# Pulse_Oximeter.net
KiCad netlist of a schematic drawn in EAGLE
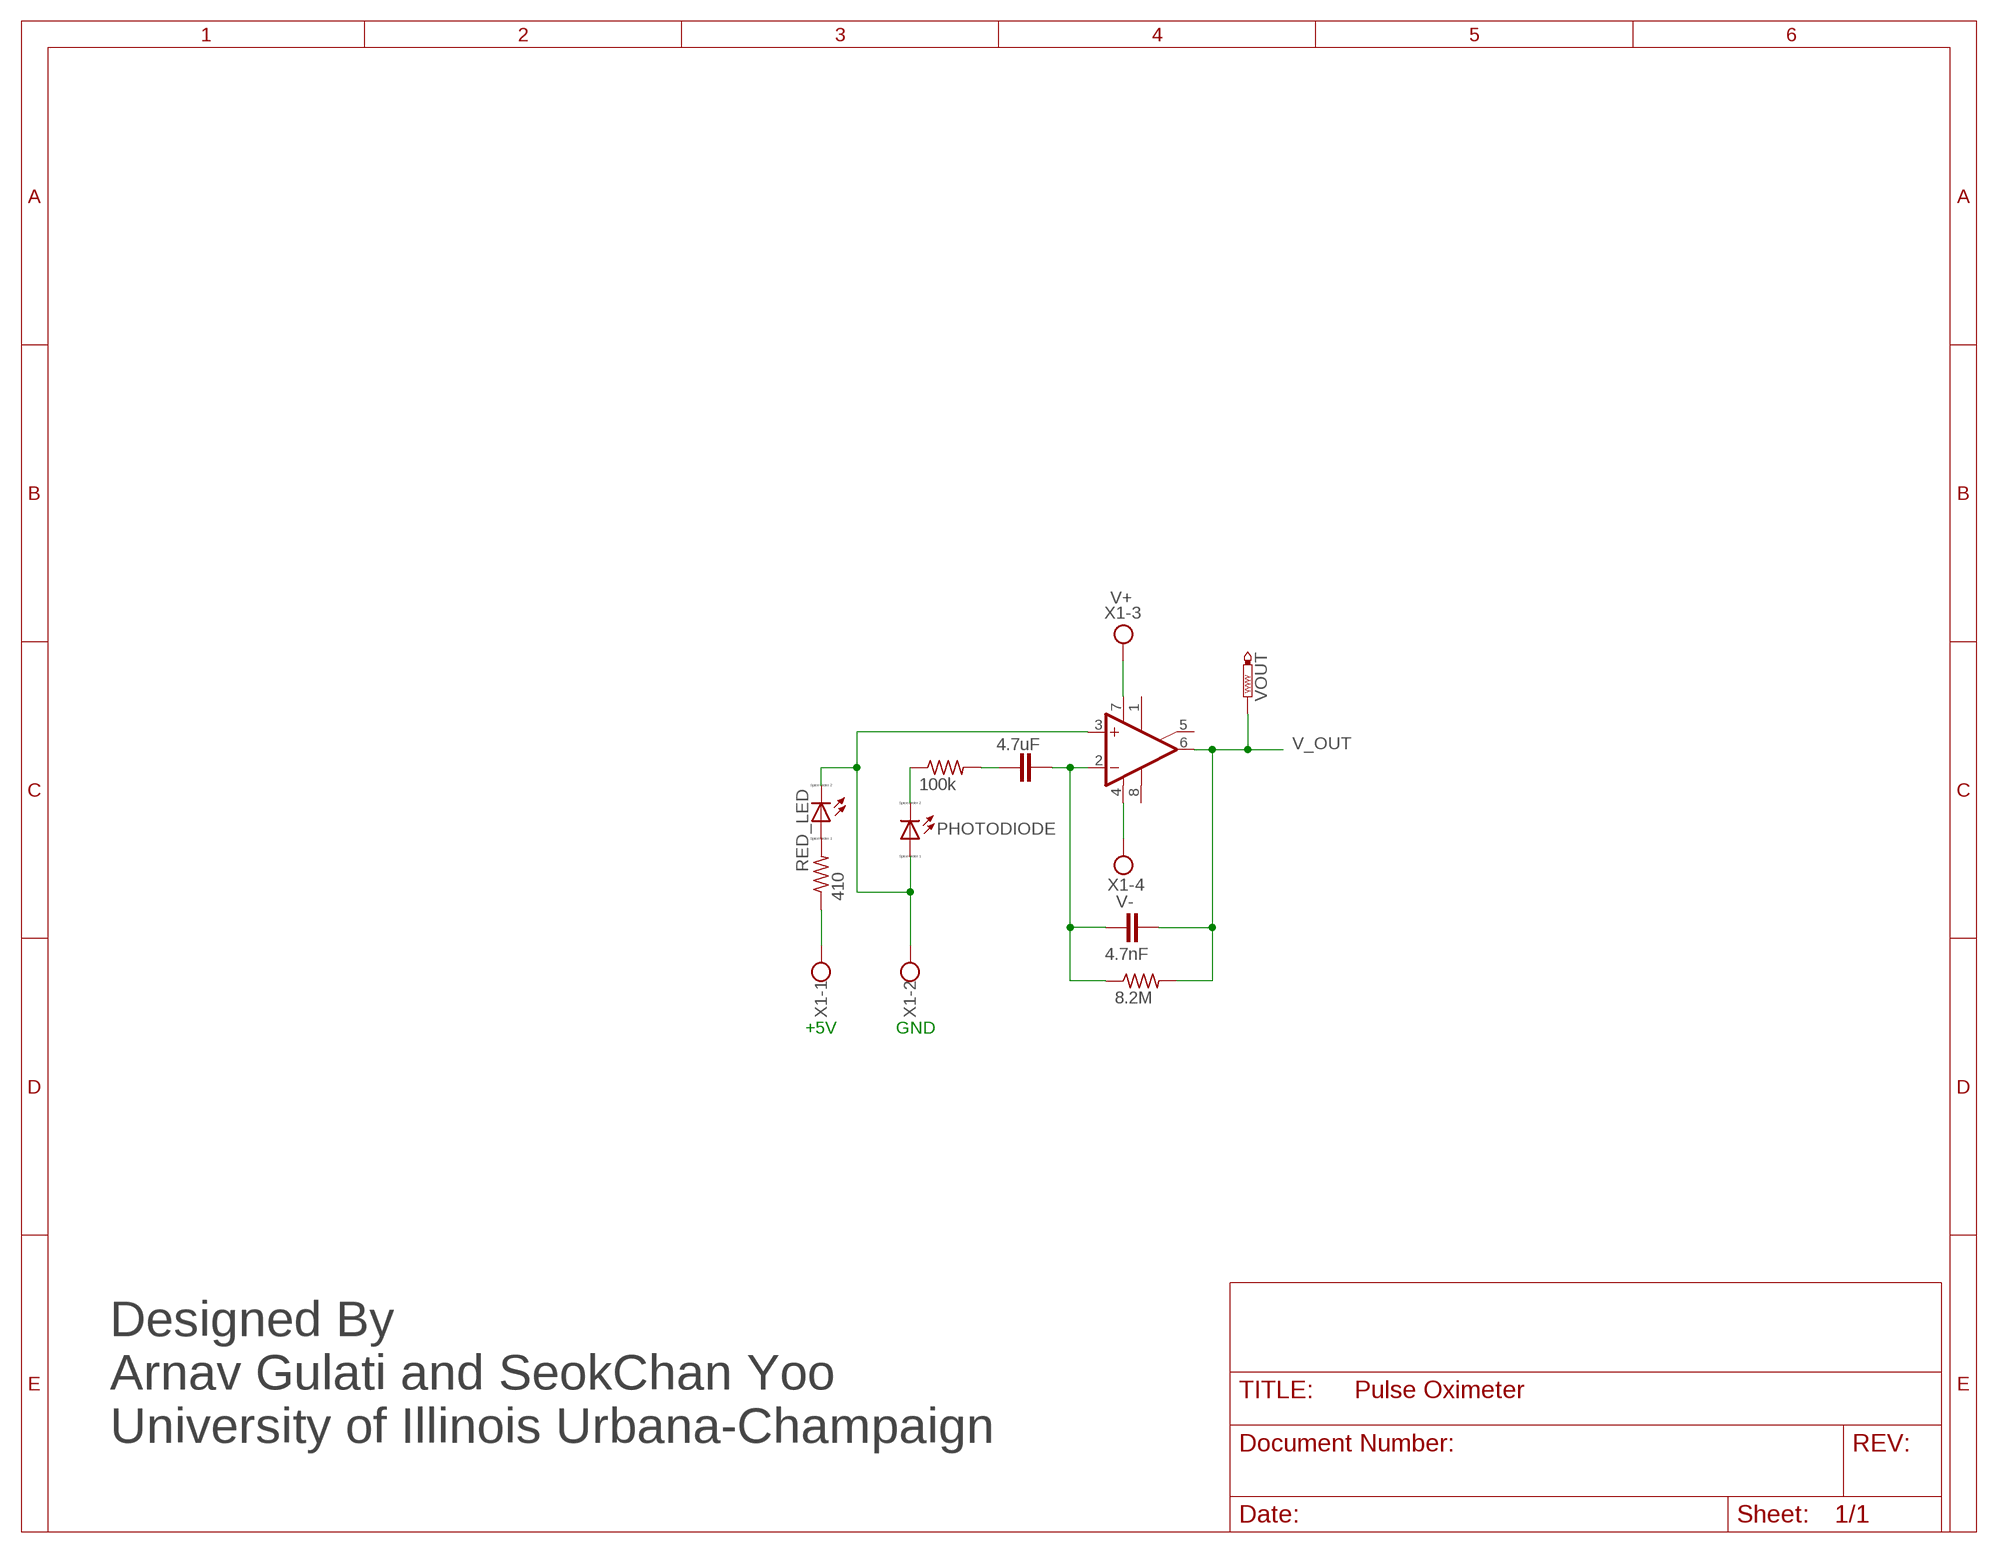
[diagram p0: schematic, sheet 1]

(export (version "E")
  (design (tool "Eeschema 10.0.6"))
  (components
    (comp (ref "C1")
      (value "4.7uF")
      (footprint "eagle-import:C2.5-3")
      (libsource (lib "eagle-import") (part "C2,5-3"))
    )
    (comp (ref "C2")
      (value "4.7nF")
      (footprint "eagle-import:C2.5-3")
      (libsource (lib "eagle-import") (part "C2,5-3"))
    )
    (comp (ref "IC1")
      (value "LM741P")
      (footprint "eagle-import:DIL08")
      (libsource (lib "eagle-import") (part "741PLM"))
    )
    (comp (ref "PHOTODIODE")
      (value "LED_ELD260")
      (footprint "eagle-import:LED_LD260")
      (libsource (lib "eagle-import") (part "LED_ELD260"))
    )
    (comp (ref "R1")
      (value "100k")
      (footprint "eagle-import:0204_5")
      (libsource (lib "eagle-import") (part "R-US_0204/5"))
    )
    (comp (ref "R2")
      (value "8.2M")
      (footprint "eagle-import:0204_5")
      (libsource (lib "eagle-import") (part "R-US_0204/5"))
    )
    (comp (ref "R3")
      (value "410")
      (footprint "eagle-import:0204_5")
      (libsource (lib "eagle-import") (part "R-US_0204/5"))
    )
    (comp (ref "RED_LED")
      (value "LED_ELD260")
      (footprint "eagle-import:LED_LD260")
      (libsource (lib "eagle-import") (part "LED_ELD260"))
    )
    (comp (ref "VOUT")
      (value "PTR1PAD1-13")
      (footprint "eagle-import:P1-13")
      (libsource (lib "eagle-import") (part "PTR1PAD1-13"))
    )
    (comp (ref "X1")
      (value "W237-4")
      (footprint "eagle-import:W237-4")
      (libsource (lib "eagle-import") (part "W237-4"))
    )
  )
  (nets
    (net (code "1") (name "/V+") (class "Default")
      (node (ref "IC1") (pin "7") (pinfunction "V+_7") (pintype "power_in"))
      (node (ref "X1") (pin "3") (pinfunction "KL_3") (pintype "passive"))
    )
    (net (code "2") (name "/V-") (class "Default")
      (node (ref "IC1") (pin "4") (pinfunction "V-_4") (pintype "power_in"))
      (node (ref "X1") (pin "4") (pinfunction "KL_4") (pintype "passive"))
    )
    (net (code "3") (name "/V_OUT") (class "Default")
      (node (ref "C2") (pin "2") (pinfunction "2_2") (pintype "passive"))
      (node (ref "IC1") (pin "6") (pinfunction "OUT_6") (pintype "output"))
      (node (ref "R2") (pin "2") (pinfunction "2_2") (pintype "passive"))
      (node (ref "VOUT") (pin "TP") (pinfunction "TP_TP") (pintype "input"))
    )
    (net (code "4") (name "Net-(C1-Pad1)") (class "Default")
      (node (ref "C1") (pin "1") (pinfunction "1_1") (pintype "passive"))
      (node (ref "R1") (pin "2") (pinfunction "2_2") (pintype "passive"))
    )
    (net (code "5") (name "Net-(IC1-+IN)") (class "Default")
      (node (ref "IC1") (pin "3") (pinfunction "+IN_3") (pintype "input"))
      (node (ref "PHOTODIODE") (pin "A") (pinfunction "A_A") (pintype "passive"))
      (node (ref "RED_LED") (pin "K") (pinfunction "C_K") (pintype "passive"))
      (node (ref "X1") (pin "2") (pinfunction "KL_2") (pintype "passive"))
    )
    (net (code "6") (name "Net-(IC1--IN)") (class "Default")
      (node (ref "C1") (pin "2") (pinfunction "2_2") (pintype "passive"))
      (node (ref "C2") (pin "1") (pinfunction "1_1") (pintype "passive"))
      (node (ref "IC1") (pin "2") (pinfunction "-IN_2") (pintype "input"))
      (node (ref "R2") (pin "1") (pinfunction "1_1") (pintype "passive"))
    )
    (net (code "7") (name "Net-(PHOTODIODE-C)") (class "Default")
      (node (ref "PHOTODIODE") (pin "K") (pinfunction "C_K") (pintype "passive"))
      (node (ref "R1") (pin "1") (pinfunction "1_1") (pintype "passive"))
    )
    (net (code "8") (name "Net-(R3-Pad2)") (class "Default")
      (node (ref "R3") (pin "2") (pinfunction "2_2") (pintype "passive"))
      (node (ref "RED_LED") (pin "A") (pinfunction "A_A") (pintype "passive"))
    )
    (net (code "9") (name "Net-(X1A-KL)") (class "Default")
      (node (ref "R3") (pin "1") (pinfunction "1_1") (pintype "passive"))
      (node (ref "X1") (pin "1") (pinfunction "KL_1") (pintype "passive"))
    )
    (net (code "10") (name "unconnected-(IC1-ON1-Pad1)") (class "Default")
      (node (ref "IC1") (pin "1") (pinfunction "ON1_1") (pintype "passive"))
    )
    (net (code "11") (name "unconnected-(IC1-ON2-Pad5)") (class "Default")
      (node (ref "IC1") (pin "5") (pinfunction "ON2_5") (pintype "passive"))
    )
    (net (code "12") (name "unconnected-(IC1-OPT-Pad8)") (class "Default")
      (node (ref "IC1") (pin "8") (pinfunction "OPT_8") (pintype "passive"))
    )
  )
)
